# Power.net
KiCad netlist of a schematic drawn in Altium Designer
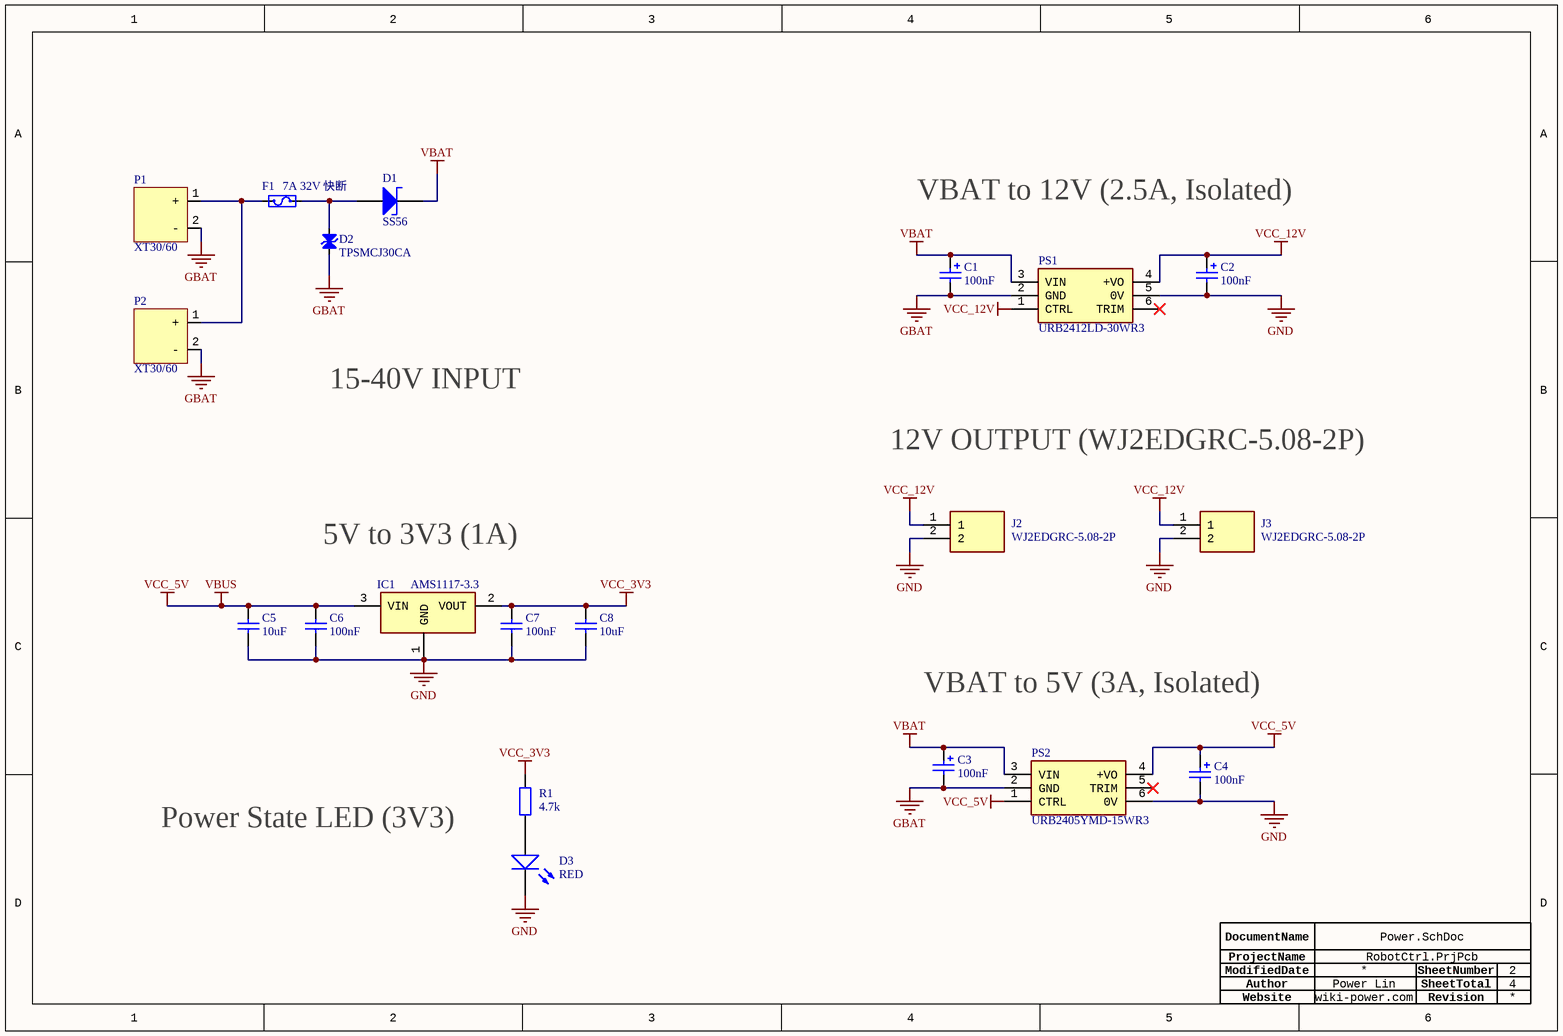
[diagram p0: Power.SchDoc]

(export (version "E")
  (design (tool "Eeschema 10.0.6"))
  (components
    (comp (ref "C1")
      (value "100nF")
      (footprint "CAP-AUX-3216")
      (description "KM101M050F115A")
      (libsource (lib "Power_Lib_Altium") (part "CAP-POL"))
    )
    (comp (ref "C2")
      (value "100nF")
      (footprint "CAP-AUX-3216")
      (description "KM101M050F115A")
      (libsource (lib "Power_Lib_Altium") (part "CAP-POL"))
    )
    (comp (ref "C3")
      (value "100nF")
      (footprint "CAP-AUX-3216")
      (description "KM101M050F115A")
      (libsource (lib "Power_Lib_Altium") (part "CAP-POL"))
    )
    (comp (ref "C4")
      (value "100nF")
      (footprint "CAP-AUX-3216")
      (description "KM101M050F115A")
      (libsource (lib "Power_Lib_Altium") (part "CAP-POL"))
    )
    (comp (ref "C5")
      (value "10uF")
      (footprint "CAP-0603")
      (description "贴片电容")
      (libsource (lib "Power_Lib_Altium") (part "CAP"))
    )
    (comp (ref "C6")
      (value "100nF")
      (footprint "CAP-0603")
      (description "贴片电容")
      (libsource (lib "Power_Lib_Altium") (part "CAP"))
    )
    (comp (ref "C7")
      (value "100nF")
      (footprint "CAP-0603")
      (description "贴片电容")
      (libsource (lib "Power_Lib_Altium") (part "CAP"))
    )
    (comp (ref "C8")
      (value "10uF")
      (footprint "CAP-0603")
      (description "贴片电容")
      (libsource (lib "Power_Lib_Altium") (part "CAP"))
    )
    (comp (ref "D1")
      (value "SS56")
      (footprint "DO-214AB/SMC")
      (description "肖特基二极管")
      (libsource (lib "Power_Lib_Altium") (part "DIODE_Schottky"))
    )
    (comp (ref "D2")
      (value "TPSMCJ30CA")
      (footprint "DO-214AB/SMC")
      (libsource (lib "Power_Lib_Altium") (part "TVS_C"))
    )
    (comp (ref "D3")
      (value "RED")
      (footprint "LED-0603")
      (description "发光二极管")
      (libsource (lib "Power_Lib_Altium") (part "LED"))
    )
    (comp (ref "F1")
      (value "7A 32V 快断")
      (footprint "FUSE_1206")
      (description "0437007.WR")
      (libsource (lib "Power_Lib_Altium") (part "Fuse"))
    )
    (comp (ref "IC1")
      (value "AMS1117-3.3")
      (footprint "SOT-223")
      (description "AMS1117-3.3 1.0A")
      (fields (field (name "MANUFACTURER_PART_NUMBER") "SI2302DS") (field (name "RS PART NUMBER") "7983053P"))
      (libsource (lib "Power_Lib_Altium") (part "AMS1117"))
    )
    (comp (ref "J2")
      (value "WJ2EDGRC-5.08-2P")
      (footprint "SamacSys:SHDRRA2W105P0X508_1X2_1206X1220X830P")
      (description "Pluggable System Terminal Block 2P RoHS")
      (libsource (lib "Power_Lib_Altium") (part "WJ2EDGRC-5.08-2P"))
    )
    (comp (ref "J3")
      (value "WJ2EDGRC-5.08-2P")
      (footprint "SamacSys:SHDRRA2W105P0X508_1X2_1206X1220X830P")
      (description "Pluggable System Terminal Block 2P RoHS")
      (libsource (lib "Power_Lib_Altium") (part "WJ2EDGRC-5.08-2P"))
    )
    (comp (ref "P1")
      (value "XT30/60")
      (footprint "XT60PW-M")
      (libsource (lib "Power_Lib_Altium") (part "XT30/60"))
    )
    (comp (ref "P2")
      (value "XT30/60")
      (footprint "XT60PW-M")
      (libsource (lib "Power_Lib_Altium") (part "XT30/60"))
    )
    (comp (ref "PS1")
      (value "URB2412LD-30WR3")
      (footprint "URB2412LD30WR3")
      (description "金升阳隔离电源")
      (fields (field (name "MANUFACTURER_PART_NUMBER") "URB2412LD-30WHR3"))
      (libsource (lib "Power_Lib_Altium") (part "URB2412LD-30WR3"))
    )
    (comp (ref "PS2")
      (value "URB2405YMD-15WR3")
      (footprint "URB2405YMD15WR3")
      (description "金升阳隔离电源")
      (fields (field (name "MANUFACTURER_PART_NUMBER") "URB2405YMD-10WR3"))
      (libsource (lib "Power_Lib_Altium") (part "URB2405YMD-15WR3"))
    )
    (comp (ref "R1")
      (value "4.7k")
      (footprint "R-0603")
      (description "贴片电阻")
      (libsource (lib "Power_Lib_Altium") (part "RES"))
    )
  )
  (nets
    (net (code "1") (name "GBAT") (class "Default")
      (node (ref "C1") (pin "2") (pinfunction "2_2") (pintype "passive"))
      (node (ref "C3") (pin "2") (pinfunction "2_2") (pintype "passive"))
      (node (ref "D2") (pin "1") (pinfunction "1_1") (pintype "passive"))
      (node (ref "P1") (pin "2") (pinfunction "-_2") (pintype "passive"))
      (node (ref "P2") (pin "2") (pinfunction "-_2") (pintype "passive"))
      (node (ref "PS1") (pin "2") (pinfunction "GND_2") (pintype "passive"))
      (node (ref "PS2") (pin "2") (pinfunction "GND_2") (pintype "passive"))
    )
    (net (code "2") (name "GND") (class "Default")
      (node (ref "C2") (pin "2") (pinfunction "2_2") (pintype "passive"))
      (node (ref "C4") (pin "2") (pinfunction "2_2") (pintype "passive"))
      (node (ref "C5") (pin "1") (pinfunction "1_1") (pintype "passive"))
      (node (ref "C6") (pin "1") (pinfunction "1_1") (pintype "passive"))
      (node (ref "C7") (pin "1") (pinfunction "1_1") (pintype "passive"))
      (node (ref "C8") (pin "1") (pinfunction "1_1") (pintype "passive"))
      (node (ref "D3") (pin "K") (pinfunction "K_K") (pintype "passive"))
      (node (ref "IC1") (pin "1") (pinfunction "GND_1") (pintype "passive"))
      (node (ref "J2") (pin "2") (pinfunction "2_2") (pintype "passive"))
      (node (ref "J3") (pin "2") (pinfunction "2_2") (pintype "passive"))
      (node (ref "PS1") (pin "5") (pinfunction "0V_5") (pintype "passive"))
      (node (ref "PS2") (pin "6") (pinfunction "0V_6") (pintype "passive"))
    )
    (net (code "3") (name "Net-(D1-A)") (class "Default")
      (node (ref "D1") (pin "1") (pinfunction "A_1") (pintype "passive"))
      (node (ref "D2") (pin "2") (pinfunction "2_2") (pintype "passive"))
      (node (ref "F1") (pin "2") (pinfunction "2_2") (pintype "passive"))
    )
    (net (code "4") (name "Net-(D3-PadA)") (class "Default")
      (node (ref "D3") (pin "A") (pinfunction "A_A") (pintype "passive"))
      (node (ref "R1") (pin "1") (pinfunction "1_1") (pintype "passive"))
    )
    (net (code "5") (name "Net-(P1-+)") (class "Default")
      (node (ref "F1") (pin "1") (pinfunction "1_1") (pintype "passive"))
      (node (ref "P1") (pin "1") (pinfunction "+_1") (pintype "passive"))
      (node (ref "P2") (pin "1") (pinfunction "+_1") (pintype "passive"))
    )
    (net (code "6") (name "VBAT") (class "Default")
      (node (ref "C1") (pin "1") (pinfunction "1_1") (pintype "passive"))
      (node (ref "C3") (pin "1") (pinfunction "1_1") (pintype "passive"))
      (node (ref "D1") (pin "2") (pinfunction "K_2") (pintype "passive"))
      (node (ref "PS1") (pin "3") (pinfunction "VIN_3") (pintype "passive"))
      (node (ref "PS2") (pin "3") (pinfunction "VIN_3") (pintype "passive"))
    )
    (net (code "7") (name "VBUS") (class "Default")
      (node (ref "C4") (pin "1") (pinfunction "1_1") (pintype "passive"))
      (node (ref "C5") (pin "2") (pinfunction "2_2") (pintype "passive"))
      (node (ref "C6") (pin "2") (pinfunction "2_2") (pintype "passive"))
      (node (ref "IC1") (pin "3") (pinfunction "VIN_3") (pintype "passive"))
      (node (ref "PS2") (pin "1") (pinfunction "CTRL_1") (pintype "passive"))
      (node (ref "PS2") (pin "4") (pinfunction "+VO_4") (pintype "passive"))
    )
    (net (code "8") (name "VCC_3V3") (class "Default")
      (node (ref "C7") (pin "2") (pinfunction "2_2") (pintype "passive"))
      (node (ref "C8") (pin "2") (pinfunction "2_2") (pintype "passive"))
      (node (ref "IC1") (pin "2") (pinfunction "VOUT_2") (pintype "passive"))
      (node (ref "R1") (pin "2") (pinfunction "2_2") (pintype "passive"))
    )
    (net (code "9") (name "VCC_12V") (class "Default")
      (node (ref "C2") (pin "1") (pinfunction "1_1") (pintype "passive"))
      (node (ref "J2") (pin "1") (pinfunction "1_1") (pintype "passive"))
      (node (ref "J3") (pin "1") (pinfunction "1_1") (pintype "passive"))
      (node (ref "PS1") (pin "1") (pinfunction "CTRL_1") (pintype "passive"))
      (node (ref "PS1") (pin "4") (pinfunction "+VO_4") (pintype "passive"))
    )
    (net (code "10") (name "unconnected-(PS1-TRIM-Pad6)") (class "Default")
      (node (ref "PS1") (pin "6") (pinfunction "TRIM_6") (pintype "passive+no_connect"))
    )
    (net (code "11") (name "unconnected-(PS2-TRIM-Pad5)") (class "Default")
      (node (ref "PS2") (pin "5") (pinfunction "TRIM_5") (pintype "passive+no_connect"))
    )
  )
)
